# DDR.net
KiCad netlist of a schematic drawn in Altium Designer
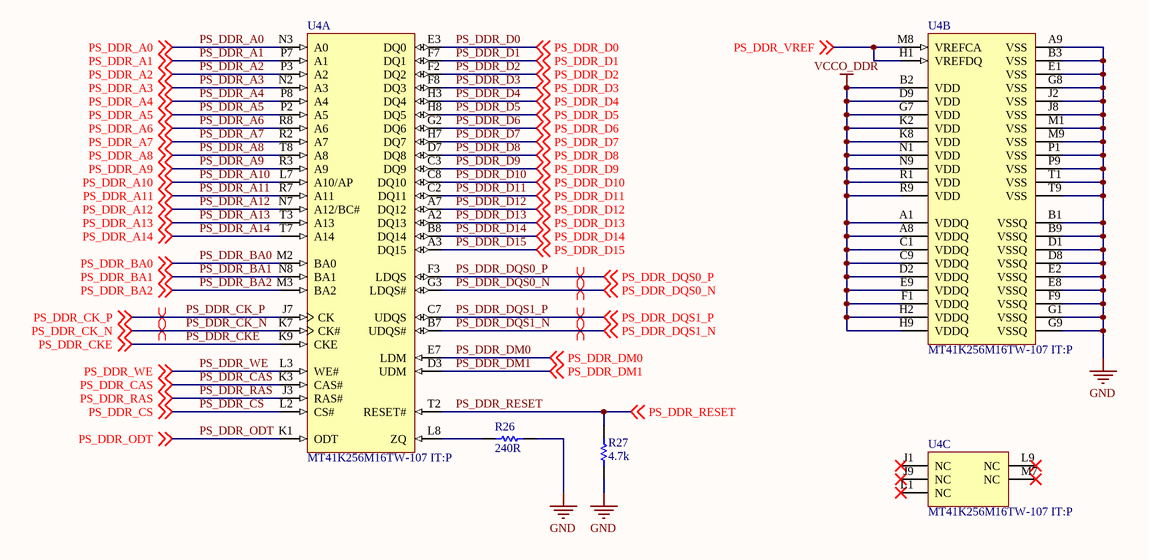
[diagram p0: DDR.SchDoc]

(export (version "E")
  (design (tool "Eeschema 10.0.6"))
  (components
    (comp (ref "R26")
      (value "240R")
      (footprint "RESC0603(1608)_N")
      (description "240R 0.1W 1% 0603 (1608 Metric)  SMD")
      (fields (field (name "POWER") "0.1 W") (field (name "TOLERANCE") "1 %"))
      (libsource (lib "Altium Content Vault") (part "RES"))
    )
    (comp (ref "R27")
      (value "4.7k")
      (footprint "RESC1608X55X25LL10T15")
      (description "Chip Resistor, 4.7 KOhm, +/- 1%, 0.1 W, -55 to 155 degC, 0603 (1608 Metric), RoHS, Tape and Reel")
      (fields (field (name "MANUFACTURER") "Yageo") (field (name "TOLERANCE") "1%"))
      (libsource (lib "Altium Content Vault") (part "RES-2"))
    )
    (comp (ref "U4")
      (value "MT41K256M16TW-107 IT:P")
      (footprint "MICT-TW-96")
      (description "Automotive DDR3L SDRAM, 4 GB, 933 MHz, 1.283 to 1.45 V, -40 to 95 degC, 96-Pin TFBGA, RoHS, Tray")
      (fields (field (name "MANUFACTURER") "Micron"))
      (libsource (lib "Altium Content Vault") (part "MICT-MT41K256M16-TW-96"))
    )
  )
  (nets
    (net (code "1") (name "GND") (class "Default")
      (node (ref "R26") (pin "2") (pinfunction "2_2") (pintype "passive"))
      (node (ref "R27") (pin "1") (pinfunction "1_1") (pintype "passive"))
      (node (ref "U4") (pin "A9") (pinfunction "VSS_A9") (pintype "power_in"))
      (node (ref "U4") (pin "B1") (pinfunction "VSSQ_B1") (pintype "power_in"))
      (node (ref "U4") (pin "B3") (pinfunction "VSS_B3") (pintype "power_in"))
      (node (ref "U4") (pin "B9") (pinfunction "VSSQ_B9") (pintype "power_in"))
      (node (ref "U4") (pin "D1") (pinfunction "VSSQ_D1") (pintype "power_in"))
      (node (ref "U4") (pin "D8") (pinfunction "VSSQ_D8") (pintype "power_in"))
      (node (ref "U4") (pin "E1") (pinfunction "VSS_E1") (pintype "power_in"))
      (node (ref "U4") (pin "E2") (pinfunction "VSSQ_E2") (pintype "power_in"))
      (node (ref "U4") (pin "E8") (pinfunction "VSSQ_E8") (pintype "power_in"))
      (node (ref "U4") (pin "F9") (pinfunction "VSSQ_F9") (pintype "power_in"))
      (node (ref "U4") (pin "G1") (pinfunction "VSSQ_G1") (pintype "power_in"))
      (node (ref "U4") (pin "G8") (pinfunction "VSS_G8") (pintype "power_in"))
      (node (ref "U4") (pin "G9") (pinfunction "VSSQ_G9") (pintype "power_in"))
      (node (ref "U4") (pin "J2") (pinfunction "VSS_J2") (pintype "power_in"))
      (node (ref "U4") (pin "J8") (pinfunction "VSS_J8") (pintype "power_in"))
      (node (ref "U4") (pin "M1") (pinfunction "VSS_M1") (pintype "power_in"))
      (node (ref "U4") (pin "M9") (pinfunction "VSS_M9") (pintype "power_in"))
      (node (ref "U4") (pin "P1") (pinfunction "VSS_P1") (pintype "power_in"))
      (node (ref "U4") (pin "P9") (pinfunction "VSS_P9") (pintype "power_in"))
      (node (ref "U4") (pin "T1") (pinfunction "VSS_T1") (pintype "power_in"))
      (node (ref "U4") (pin "T9") (pinfunction "VSS_T9") (pintype "power_in"))
    )
    (net (code "2") (name "Net-(U4A-ZQ)") (class "Default")
      (node (ref "R26") (pin "1") (pinfunction "1_1") (pintype "passive"))
      (node (ref "U4") (pin "L8") (pinfunction "ZQ_L8") (pintype "input"))
    )
    (net (code "3") (name "PS_DDR_A0") (class "Default")
      (node (ref "U4") (pin "N3") (pinfunction "A0_N3") (pintype "input"))
    )
    (net (code "4") (name "PS_DDR_A1") (class "Default")
      (node (ref "U4") (pin "P7") (pinfunction "A1_P7") (pintype "input"))
    )
    (net (code "5") (name "PS_DDR_A2") (class "Default")
      (node (ref "U4") (pin "P3") (pinfunction "A2_P3") (pintype "input"))
    )
    (net (code "6") (name "PS_DDR_A3") (class "Default")
      (node (ref "U4") (pin "N2") (pinfunction "A3_N2") (pintype "input"))
    )
    (net (code "7") (name "PS_DDR_A4") (class "Default")
      (node (ref "U4") (pin "P8") (pinfunction "A4_P8") (pintype "input"))
    )
    (net (code "8") (name "PS_DDR_A5") (class "Default")
      (node (ref "U4") (pin "P2") (pinfunction "A5_P2") (pintype "input"))
    )
    (net (code "9") (name "PS_DDR_A6") (class "Default")
      (node (ref "U4") (pin "R8") (pinfunction "A6_R8") (pintype "input"))
    )
    (net (code "10") (name "PS_DDR_A7") (class "Default")
      (node (ref "U4") (pin "R2") (pinfunction "A7_R2") (pintype "input"))
    )
    (net (code "11") (name "PS_DDR_A8") (class "Default")
      (node (ref "U4") (pin "T8") (pinfunction "A8_T8") (pintype "input"))
    )
    (net (code "12") (name "PS_DDR_A9") (class "Default")
      (node (ref "U4") (pin "R3") (pinfunction "A9_R3") (pintype "input"))
    )
    (net (code "13") (name "PS_DDR_A10") (class "Default")
      (node (ref "U4") (pin "L7") (pinfunction "A10/AP_L7") (pintype "input"))
    )
    (net (code "14") (name "PS_DDR_A11") (class "Default")
      (node (ref "U4") (pin "R7") (pinfunction "A11_R7") (pintype "input"))
    )
    (net (code "15") (name "PS_DDR_A12") (class "Default")
      (node (ref "U4") (pin "N7") (pinfunction "A12/BC#_N7") (pintype "input"))
    )
    (net (code "16") (name "PS_DDR_A13") (class "Default")
      (node (ref "U4") (pin "T3") (pinfunction "A13_T3") (pintype "input"))
    )
    (net (code "17") (name "PS_DDR_A14") (class "Default")
      (node (ref "U4") (pin "T7") (pinfunction "A14_T7") (pintype "input"))
    )
    (net (code "18") (name "PS_DDR_BA0") (class "Default")
      (node (ref "U4") (pin "M2") (pinfunction "BA0_M2") (pintype "input"))
    )
    (net (code "19") (name "PS_DDR_BA1") (class "Default")
      (node (ref "U4") (pin "N8") (pinfunction "BA1_N8") (pintype "input"))
    )
    (net (code "20") (name "PS_DDR_BA2") (class "Default")
      (node (ref "U4") (pin "M3") (pinfunction "BA2_M3") (pintype "input"))
    )
    (net (code "21") (name "PS_DDR_CAS") (class "Default")
      (node (ref "U4") (pin "K3") (pinfunction "CAS#_K3") (pintype "input"))
    )
    (net (code "22") (name "PS_DDR_CKE") (class "Default")
      (node (ref "U4") (pin "K9") (pinfunction "CKE_K9") (pintype "input"))
    )
    (net (code "23") (name "PS_DDR_CK_N") (class "Default")
      (node (ref "U4") (pin "K7") (pinfunction "CK#_K7") (pintype "input"))
    )
    (net (code "24") (name "PS_DDR_CK_P") (class "Default")
      (node (ref "U4") (pin "J7") (pinfunction "CK_J7") (pintype "input"))
    )
    (net (code "25") (name "PS_DDR_CS") (class "Default")
      (node (ref "U4") (pin "L2") (pinfunction "CS#_L2") (pintype "input"))
    )
    (net (code "26") (name "PS_DDR_D0") (class "Default")
      (node (ref "U4") (pin "E3") (pinfunction "DQ0_E3") (pintype "bidirectional"))
    )
    (net (code "27") (name "PS_DDR_D1") (class "Default")
      (node (ref "U4") (pin "F7") (pinfunction "DQ1_F7") (pintype "bidirectional"))
    )
    (net (code "28") (name "PS_DDR_D2") (class "Default")
      (node (ref "U4") (pin "F2") (pinfunction "DQ2_F2") (pintype "bidirectional"))
    )
    (net (code "29") (name "PS_DDR_D3") (class "Default")
      (node (ref "U4") (pin "F8") (pinfunction "DQ3_F8") (pintype "bidirectional"))
    )
    (net (code "30") (name "PS_DDR_D4") (class "Default")
      (node (ref "U4") (pin "H3") (pinfunction "DQ4_H3") (pintype "bidirectional"))
    )
    (net (code "31") (name "PS_DDR_D5") (class "Default")
      (node (ref "U4") (pin "H8") (pinfunction "DQ5_H8") (pintype "bidirectional"))
    )
    (net (code "32") (name "PS_DDR_D6") (class "Default")
      (node (ref "U4") (pin "G2") (pinfunction "DQ6_G2") (pintype "bidirectional"))
    )
    (net (code "33") (name "PS_DDR_D7") (class "Default")
      (node (ref "U4") (pin "H7") (pinfunction "DQ7_H7") (pintype "bidirectional"))
    )
    (net (code "34") (name "PS_DDR_D8") (class "Default")
      (node (ref "U4") (pin "D7") (pinfunction "DQ8_D7") (pintype "bidirectional"))
    )
    (net (code "35") (name "PS_DDR_D9") (class "Default")
      (node (ref "U4") (pin "C3") (pinfunction "DQ9_C3") (pintype "bidirectional"))
    )
    (net (code "36") (name "PS_DDR_D10") (class "Default")
      (node (ref "U4") (pin "C8") (pinfunction "DQ10_C8") (pintype "bidirectional"))
    )
    (net (code "37") (name "PS_DDR_D11") (class "Default")
      (node (ref "U4") (pin "C2") (pinfunction "DQ11_C2") (pintype "bidirectional"))
    )
    (net (code "38") (name "PS_DDR_D12") (class "Default")
      (node (ref "U4") (pin "A7") (pinfunction "DQ12_A7") (pintype "bidirectional"))
    )
    (net (code "39") (name "PS_DDR_D13") (class "Default")
      (node (ref "U4") (pin "A2") (pinfunction "DQ13_A2") (pintype "bidirectional"))
    )
    (net (code "40") (name "PS_DDR_D14") (class "Default")
      (node (ref "U4") (pin "B8") (pinfunction "DQ14_B8") (pintype "bidirectional"))
    )
    (net (code "41") (name "PS_DDR_D15") (class "Default")
      (node (ref "U4") (pin "A3") (pinfunction "DQ15_A3") (pintype "bidirectional"))
    )
    (net (code "42") (name "PS_DDR_DM0") (class "Default")
      (node (ref "U4") (pin "E7") (pinfunction "LDM_E7") (pintype "input"))
    )
    (net (code "43") (name "PS_DDR_DM1") (class "Default")
      (node (ref "U4") (pin "D3") (pinfunction "UDM_D3") (pintype "input"))
    )
    (net (code "44") (name "PS_DDR_DQS0_N") (class "Default")
      (node (ref "U4") (pin "G3") (pinfunction "LDQS#_G3") (pintype "bidirectional"))
    )
    (net (code "45") (name "PS_DDR_DQS0_P") (class "Default")
      (node (ref "U4") (pin "F3") (pinfunction "LDQS_F3") (pintype "bidirectional"))
    )
    (net (code "46") (name "PS_DDR_DQS1_N") (class "Default")
      (node (ref "U4") (pin "B7") (pinfunction "UDQS#_B7") (pintype "bidirectional"))
    )
    (net (code "47") (name "PS_DDR_DQS1_P") (class "Default")
      (node (ref "U4") (pin "C7") (pinfunction "UDQS_C7") (pintype "bidirectional"))
    )
    (net (code "48") (name "PS_DDR_ODT") (class "Default")
      (node (ref "U4") (pin "K1") (pinfunction "ODT_K1") (pintype "input"))
    )
    (net (code "49") (name "PS_DDR_RAS") (class "Default")
      (node (ref "U4") (pin "J3") (pinfunction "RAS#_J3") (pintype "input"))
    )
    (net (code "50") (name "PS_DDR_RESET") (class "Default")
      (node (ref "R27") (pin "2") (pinfunction "2_2") (pintype "passive"))
      (node (ref "U4") (pin "T2") (pinfunction "RESET#_T2") (pintype "input"))
    )
    (net (code "51") (name "PS_DDR_VREF") (class "Default")
      (node (ref "U4") (pin "H1") (pinfunction "VREFDQ_H1") (pintype "input"))
      (node (ref "U4") (pin "M8") (pinfunction "VREFCA_M8") (pintype "input"))
    )
    (net (code "52") (name "PS_DDR_WE") (class "Default")
      (node (ref "U4") (pin "L3") (pinfunction "WE#_L3") (pintype "input"))
    )
    (net (code "53") (name "VCCO_DDR") (class "Default")
      (node (ref "U4") (pin "A1") (pinfunction "VDDQ_A1") (pintype "power_in"))
      (node (ref "U4") (pin "A8") (pinfunction "VDDQ_A8") (pintype "power_in"))
      (node (ref "U4") (pin "B2") (pinfunction "VDD_B2") (pintype "power_in"))
      (node (ref "U4") (pin "C1") (pinfunction "VDDQ_C1") (pintype "power_in"))
      (node (ref "U4") (pin "C9") (pinfunction "VDDQ_C9") (pintype "power_in"))
      (node (ref "U4") (pin "D2") (pinfunction "VDDQ_D2") (pintype "power_in"))
      (node (ref "U4") (pin "D9") (pinfunction "VDD_D9") (pintype "power_in"))
      (node (ref "U4") (pin "E9") (pinfunction "VDDQ_E9") (pintype "power_in"))
      (node (ref "U4") (pin "F1") (pinfunction "VDDQ_F1") (pintype "power_in"))
      (node (ref "U4") (pin "G7") (pinfunction "VDD_G7") (pintype "power_in"))
      (node (ref "U4") (pin "H2") (pinfunction "VDDQ_H2") (pintype "power_in"))
      (node (ref "U4") (pin "H9") (pinfunction "VDDQ_H9") (pintype "power_in"))
      (node (ref "U4") (pin "K2") (pinfunction "VDD_K2") (pintype "power_in"))
      (node (ref "U4") (pin "K8") (pinfunction "VDD_K8") (pintype "power_in"))
      (node (ref "U4") (pin "N1") (pinfunction "VDD_N1") (pintype "power_in"))
      (node (ref "U4") (pin "N9") (pinfunction "VDD_N9") (pintype "power_in"))
      (node (ref "U4") (pin "R1") (pinfunction "VDD_R1") (pintype "power_in"))
      (node (ref "U4") (pin "R9") (pinfunction "VDD_R9") (pintype "power_in"))
    )
    (net (code "54") (name "unconnected-(U4C-NC-PadJ1)") (class "Default")
      (node (ref "U4") (pin "J1") (pinfunction "NC_J1") (pintype "passive+no_connect"))
    )
    (net (code "55") (name "unconnected-(U4C-NC-PadJ9)") (class "Default")
      (node (ref "U4") (pin "J9") (pinfunction "NC_J9") (pintype "passive+no_connect"))
    )
    (net (code "56") (name "unconnected-(U4C-NC-PadL1)") (class "Default")
      (node (ref "U4") (pin "L1") (pinfunction "NC_L1") (pintype "passive+no_connect"))
    )
    (net (code "57") (name "unconnected-(U4C-NC-PadL9)") (class "Default")
      (node (ref "U4") (pin "L9") (pinfunction "NC_L9") (pintype "passive+no_connect"))
    )
    (net (code "58") (name "unconnected-(U4C-NC-PadM7)") (class "Default")
      (node (ref "U4") (pin "M7") (pinfunction "NC_M7") (pintype "passive+no_connect"))
    )
  )
)
